# LB_BIT_o11_servo-v03_rev4_4.net
KiCad netlist of a schematic drawn in EAGLE
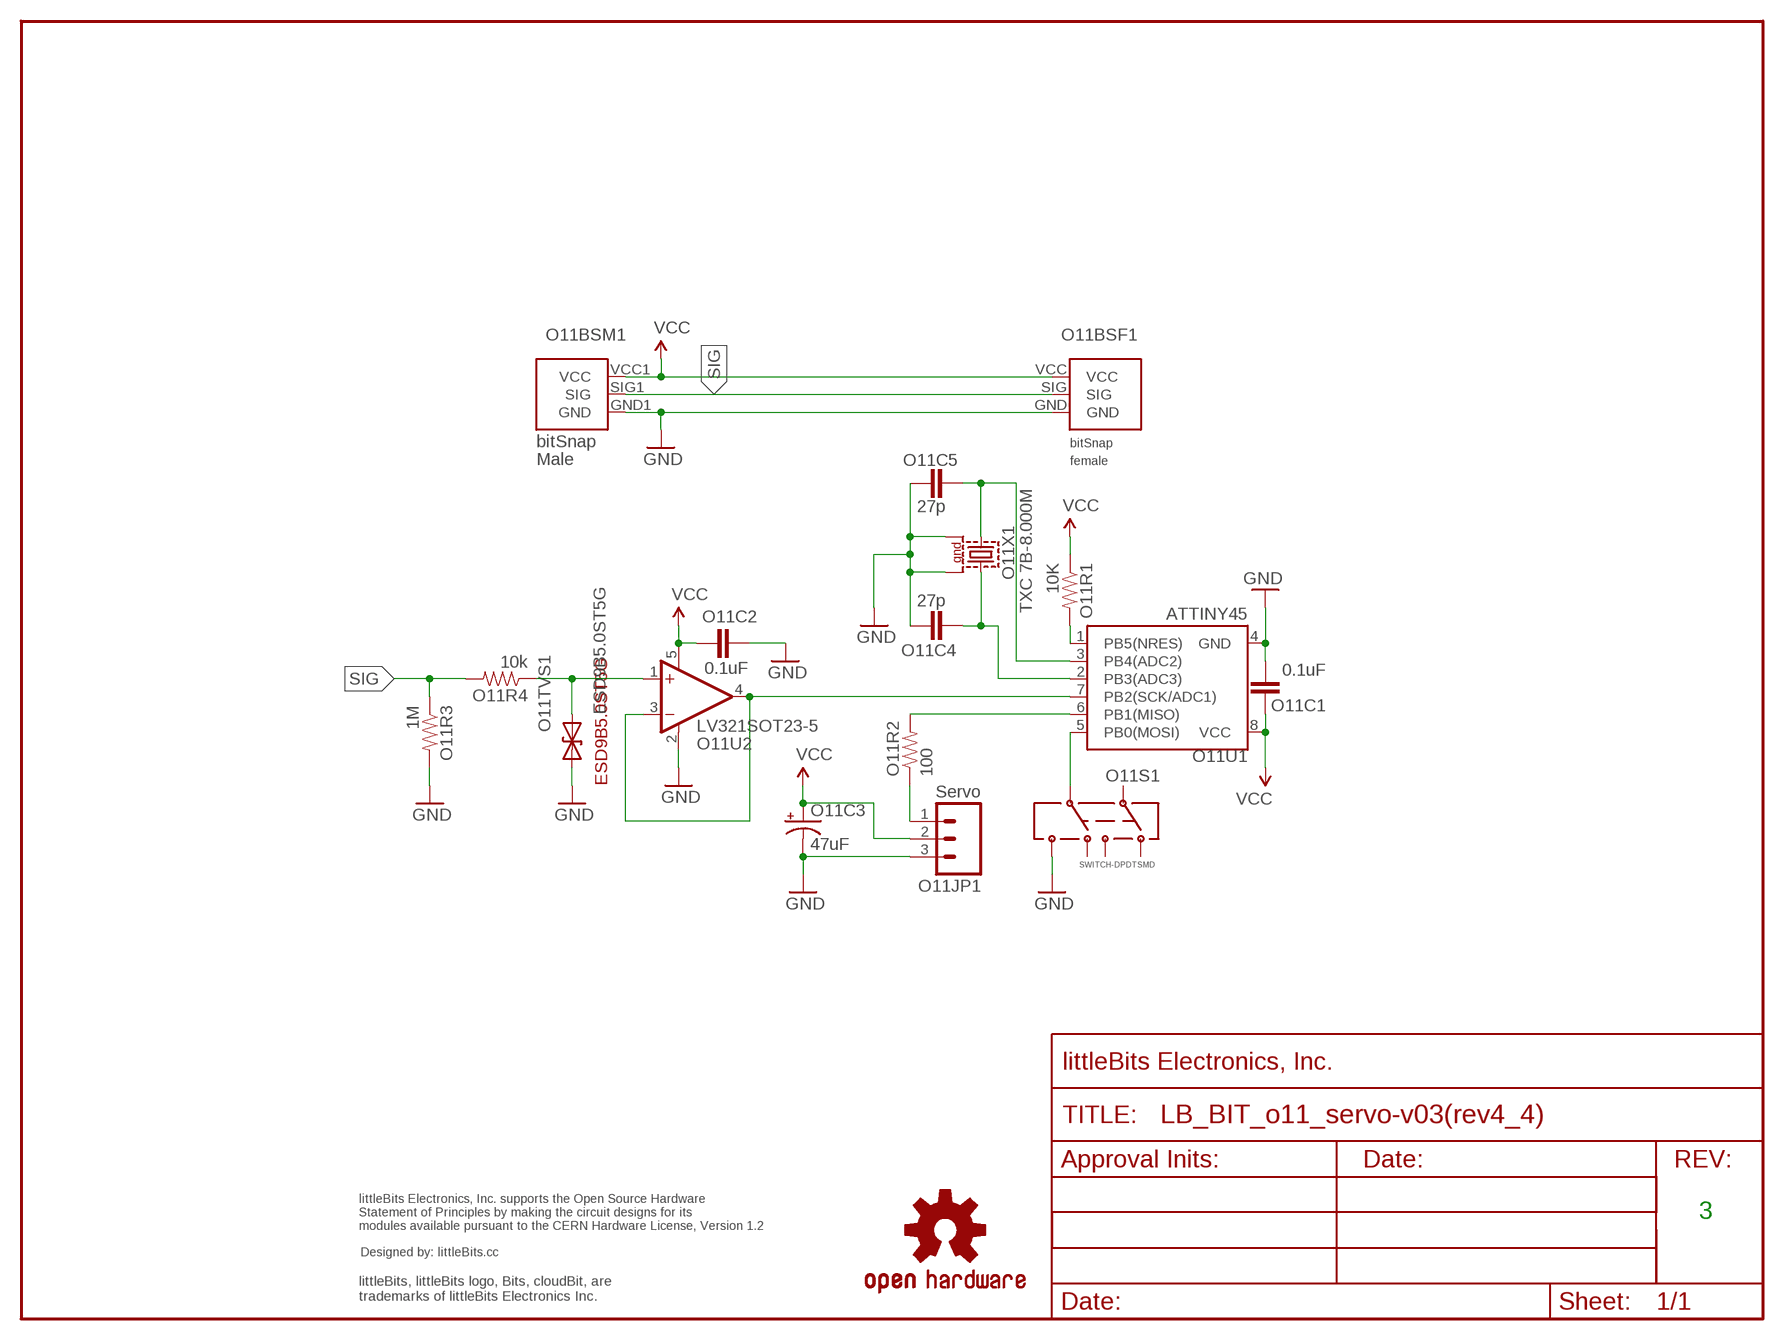
[diagram p0: schematic, sheet 1]

(export (version "E")
  (design (tool "Eeschema 10.0.6"))
  (components
    (comp (ref "O11BSF1")
      (value "BITSNAP_V03_FEMALE")
      (footprint "eagle-import:BITSNAP_V03_FEMALE")
      (libsource (lib "eagle-import") (part "BITSNAP_V03_FEMALE"))
    )
    (comp (ref "O11BSM1")
      (value "BITSNAP_V03_MALE")
      (footprint "eagle-import:BITSNAP_V03_MALE")
      (libsource (lib "eagle-import") (part "BITSNAP_V03_MALE"))
    )
    (comp (ref "O11C1")
      (value "0.1uF")
      (footprint "eagle-import:0603-CAP")
      (libsource (lib "eagle-import") (part "CAP0603-CAP"))
    )
    (comp (ref "O11C2")
      (value "0.1uF")
      (footprint "eagle-import:0603-CAP")
      (libsource (lib "eagle-import") (part "CAP0603-CAP"))
    )
    (comp (ref "O11C3")
      (value "47uF")
      (footprint "eagle-import:EIA3216")
      (libsource (lib "eagle-import") (part "CAP_POL3216"))
    )
    (comp (ref "O11C4")
      (value "27p")
      (footprint "eagle-import:0603-CAP")
      (libsource (lib "eagle-import") (part "CAP0603-CAP"))
    )
    (comp (ref "O11C5")
      (value "27p")
      (footprint "eagle-import:0603-CAP")
      (libsource (lib "eagle-import") (part "CAP0603-CAP"))
    )
    (comp (ref "O11JP1")
      (value "Servo")
      (footprint "eagle-import:1X03")
      (libsource (lib "eagle-import") (part "M03PTH"))
    )
    (comp (ref "O11R1")
      (value "10K")
      (footprint "eagle-import:0603-RES")
      (libsource (lib "eagle-import") (part "RESISTOR0603-RES"))
    )
    (comp (ref "O11R2")
      (value "100")
      (footprint "eagle-import:0603-RES")
      (libsource (lib "eagle-import") (part "RESISTOR0603-RES"))
    )
    (comp (ref "O11R3")
      (value "1M")
      (footprint "eagle-import:0603-RES")
      (libsource (lib "eagle-import") (part "RESISTOR0603-RES"))
    )
    (comp (ref "O11R4")
      (value "10k")
      (footprint "eagle-import:0603-RES")
      (libsource (lib "eagle-import") (part "RESISTOR0603-RES"))
    )
    (comp (ref "O11S1")
      (value "SWITCH-DPDTSMD")
      (footprint "eagle-import:AYZ0202")
      (libsource (lib "eagle-import") (part "SWITCH-DPDTSMD"))
    )
    (comp (ref "O11TVS1")
      (value "ESD9B5.0ST5G")
      (footprint "eagle-import:SOD-923")
      (libsource (lib "eagle-import") (part "DIODE-TVSSOD-923"))
    )
    (comp (ref "O11U1")
      (value "ATTINY45")
      (footprint "eagle-import:SO08-EIAJ")
      (libsource (lib "eagle-import") (part "ATTINY45"))
    )
    (comp (ref "O11U2")
      (value "LV321SOT23-5")
      (footprint "eagle-import:SOT23-5")
      (libsource (lib "eagle-import") (part "LV321SOT23-5"))
    )
    (comp (ref "O11X1")
      (value "TXC 7B-8.000M")
      (footprint "eagle-import:CRYSTAL-SMD-7B-SERIES-5X3.2MM")
      (fields (field (name "MFG") "TXC") (field (name "MPN") "7B SERIES"))
      (libsource (lib "eagle-import") (part "CRYSTAL-SMD-7B-SERIES-TXC"))
    )
    (comp (ref "U$1")
      (value "FRAME-LETTER-OHWOHW")
      (footprint "eagle-import:FABDWG01-OHW")
      (libsource (lib "eagle-import") (part "FRAME-LETTER-OHWOHW"))
    )
    (comp (ref "U$13")
      (value "OSHWCREDIT")
      (footprint "eagle-import:OSHWCREDIT")
      (libsource (lib "eagle-import") (part "OSHWCREDIT"))
    )
    (comp (ref "U$25")
      (value "OSHW-LOGOL")
      (footprint "eagle-import:OSHW-LOGO-L")
      (libsource (lib "eagle-import") (part "OSHW-LOGOL"))
    )
  )
  (nets
    (net (code "1") (name "GND") (class "Default")
      (node (ref "O11BSF1") (pin "GND") (pinfunction "GND_GND") (pintype "bidirectional"))
      (node (ref "O11BSM1") (pin "GND1") (pinfunction "GND_GND1") (pintype "bidirectional"))
      (node (ref "O11C1") (pin "2") (pinfunction "2_2") (pintype "passive"))
      (node (ref "O11C2") (pin "2") (pinfunction "2_2") (pintype "passive"))
      (node (ref "O11C3") (pin "-") (pinfunction "-_-") (pintype "passive"))
      (node (ref "O11C4") (pin "1") (pinfunction "1_1") (pintype "passive"))
      (node (ref "O11C5") (pin "2") (pinfunction "2_2") (pintype "passive"))
      (node (ref "O11JP1") (pin "3") (pinfunction "3_3") (pintype "passive"))
      (node (ref "O11R3") (pin "2") (pinfunction "2_2") (pintype "passive"))
      (node (ref "O11S1") (pin "6") (pinfunction "6_6") (pintype "bidirectional"))
      (node (ref "O11TVS1") (pin "1") (pinfunction "A_1") (pintype "passive"))
      (node (ref "O11U1") (pin "4") (pinfunction "GND_4") (pintype "bidirectional"))
      (node (ref "O11U2") (pin "2") (pinfunction "V-_2") (pintype "power_in"))
      (node (ref "O11X1") (pin "P$2") (pinfunction "2_P$2") (pintype "passive"))
      (node (ref "O11X1") (pin "P$4") (pinfunction "4_P$4") (pintype "passive"))
    )
    (net (code "2") (name "Net-(O11JP1-Pad1)") (class "Default")
      (node (ref "O11JP1") (pin "1") (pinfunction "1_1") (pintype "passive"))
      (node (ref "O11R2") (pin "1") (pinfunction "1_1") (pintype "passive"))
    )
    (net (code "3") (name "Net-(O11TVS1-C)") (class "Default")
      (node (ref "O11R4") (pin "1") (pinfunction "1_1") (pintype "passive"))
      (node (ref "O11TVS1") (pin "2") (pinfunction "C_2") (pintype "passive"))
      (node (ref "O11U2") (pin "1") (pinfunction "+IN_1") (pintype "input"))
    )
    (net (code "4") (name "Net-(O11U1-PB0(MOSI))") (class "Default")
      (node (ref "O11S1") (pin "5") (pinfunction "5_5") (pintype "bidirectional"))
      (node (ref "O11U1") (pin "5") (pinfunction "PB0(MOSI)_5") (pintype "bidirectional"))
    )
    (net (code "5") (name "Net-(O11U1-PB1(MISO))") (class "Default")
      (node (ref "O11R2") (pin "2") (pinfunction "2_2") (pintype "passive"))
      (node (ref "O11U1") (pin "6") (pinfunction "PB1(MISO)_6") (pintype "bidirectional"))
    )
    (net (code "6") (name "Net-(O11U1-PB2(SCK{slash}ADC1))") (class "Default")
      (node (ref "O11U1") (pin "7") (pinfunction "PB2(SCK/ADC1)_7") (pintype "bidirectional"))
      (node (ref "O11U2") (pin "3") (pinfunction "-IN_3") (pintype "input"))
      (node (ref "O11U2") (pin "4") (pinfunction "OUT_4") (pintype "output"))
    )
    (net (code "7") (name "Net-(O11U1-PB3(ADC3))") (class "Default")
      (node (ref "O11C4") (pin "2") (pinfunction "2_2") (pintype "passive"))
      (node (ref "O11U1") (pin "2") (pinfunction "PB3(ADC3)_2") (pintype "bidirectional"))
      (node (ref "O11X1") (pin "P$3") (pinfunction "3_P$3") (pintype "passive"))
    )
    (net (code "8") (name "Net-(O11U1-PB4(ADC2))") (class "Default")
      (node (ref "O11C5") (pin "1") (pinfunction "1_1") (pintype "passive"))
      (node (ref "O11U1") (pin "3") (pinfunction "PB4(ADC2)_3") (pintype "bidirectional"))
      (node (ref "O11X1") (pin "P$1") (pinfunction "1_P$1") (pintype "passive"))
    )
    (net (code "9") (name "Net-(O11U1-PB5(NRES))") (class "Default")
      (node (ref "O11R1") (pin "2") (pinfunction "2_2") (pintype "passive"))
      (node (ref "O11U1") (pin "1") (pinfunction "PB5(NRES)_1") (pintype "bidirectional"))
    )
    (net (code "10") (name "SIG") (class "Default")
      (node (ref "O11BSF1") (pin "SIG") (pinfunction "SIG_SIG") (pintype "bidirectional"))
      (node (ref "O11BSM1") (pin "SIG1") (pinfunction "SIG_SIG1") (pintype "bidirectional"))
      (node (ref "O11R3") (pin "1") (pinfunction "1_1") (pintype "passive"))
      (node (ref "O11R4") (pin "2") (pinfunction "2_2") (pintype "passive"))
    )
    (net (code "11") (name "VCC") (class "Default")
      (node (ref "O11BSF1") (pin "VCC") (pinfunction "VCC_VCC") (pintype "bidirectional"))
      (node (ref "O11BSM1") (pin "VCC1") (pinfunction "VCC_VCC1") (pintype "bidirectional"))
      (node (ref "O11C1") (pin "1") (pinfunction "1_1") (pintype "passive"))
      (node (ref "O11C2") (pin "1") (pinfunction "1_1") (pintype "passive"))
      (node (ref "O11C3") (pin "+") (pinfunction "+_+") (pintype "passive"))
      (node (ref "O11JP1") (pin "2") (pinfunction "2_2") (pintype "passive"))
      (node (ref "O11R1") (pin "1") (pinfunction "1_1") (pintype "passive"))
      (node (ref "O11U1") (pin "8") (pinfunction "VCC_8") (pintype "bidirectional"))
      (node (ref "O11U2") (pin "5") (pinfunction "V+_5") (pintype "power_in"))
    )
    (net (code "12") (name "unconnected-(O11S1-Pad1)") (class "Default")
      (node (ref "O11S1") (pin "1") (pinfunction "1_1") (pintype "bidirectional"))
    )
    (net (code "13") (name "unconnected-(O11S1-Pad2)") (class "Default")
      (node (ref "O11S1") (pin "2") (pinfunction "2_2") (pintype "bidirectional"))
    )
    (net (code "14") (name "unconnected-(O11S1-Pad3)") (class "Default")
      (node (ref "O11S1") (pin "3") (pinfunction "3_3") (pintype "bidirectional"))
    )
    (net (code "15") (name "unconnected-(O11S1-Pad4)") (class "Default")
      (node (ref "O11S1") (pin "4") (pinfunction "4_4") (pintype "bidirectional"))
    )
  )
)
